# Sheet1.net
KiCad netlist of a schematic drawn in Altium Designer
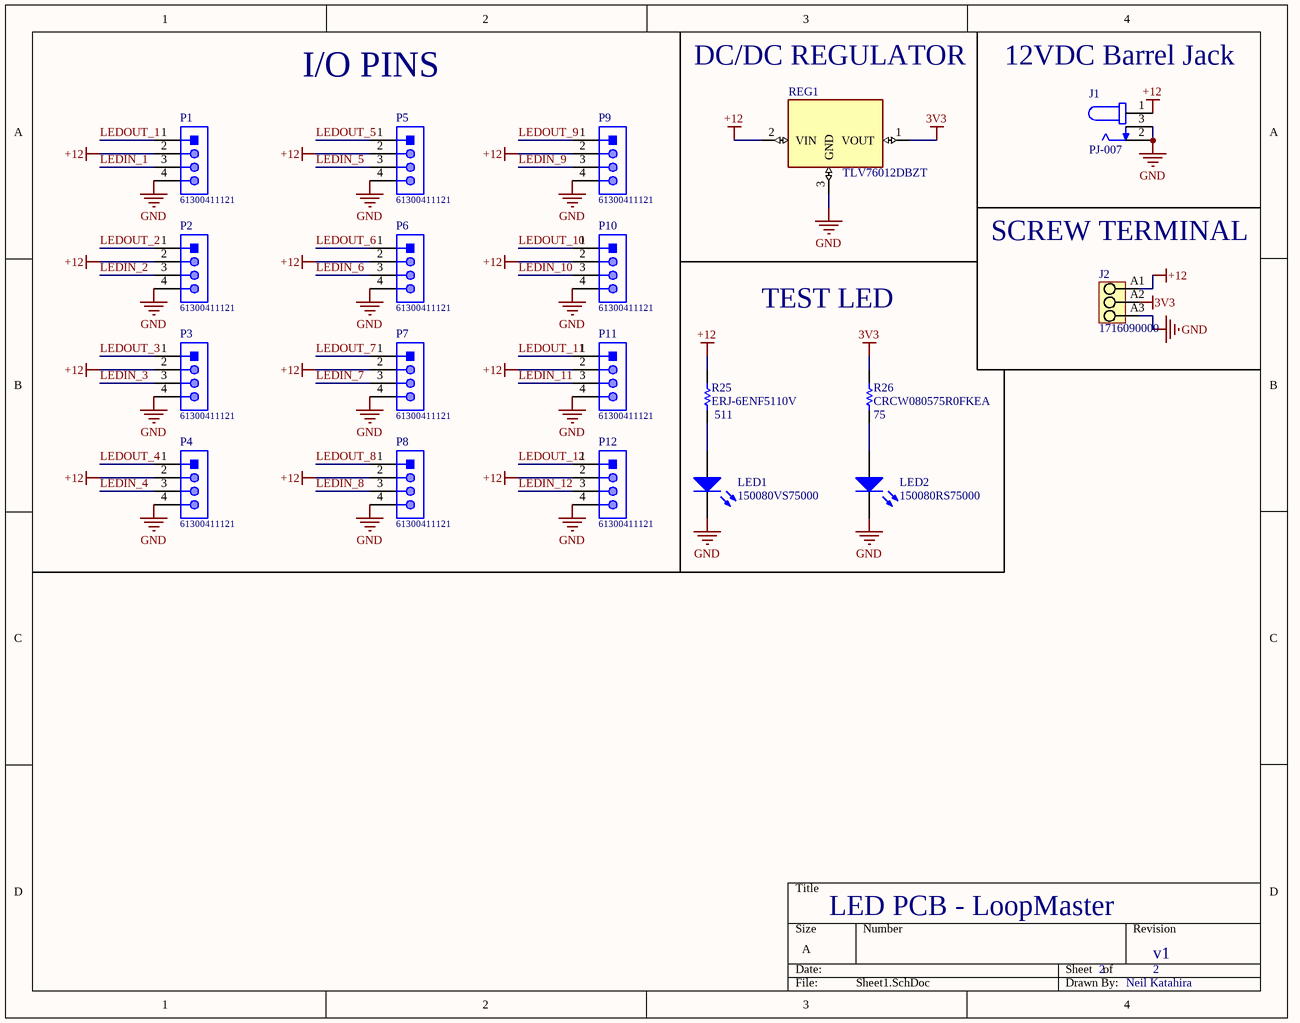
[diagram p0: Sheet1.SchDoc]

(export (version "E")
  (design (tool "Eeschema 10.0.6"))
  (components
    (comp (ref "J1")
      (value "PJ-007")
      (footprint "CUI_PJ-007")
      (description "1.3 x 4.2 mm, 2.0 A, Horizontal, Through Hole, Dc Power Jack Connector")
      (fields (field (name "MF") "CUI Devices"))
      (libsource (lib "LEDPCB") (part "PJ-007"))
    )
    (comp (ref "J2")
      (value "1716090000")
      (footprint "LM_5_08_90_03")
      (description "OMNIMATE Signal - series LM")
      (fields (field (name "MANUFACTURER") "Weidmueller"))
      (libsource (lib "Altium Content Vault") (part "Terminal_03_1x03"))
    )
    (comp (ref "LED1")
      (value "150080VS75000")
      (footprint "0805_A")
      (description "SMD mono-color Chip LED, WL-SMCW, Bright Green")
      (fields (field (name "MANUFACTURER") "Wuerth Elektronik"))
      (libsource (lib "Altium Content Vault") (part "WE-LED_K1A2-2"))
    )
    (comp (ref "LED2")
      (value "150080RS75000")
      (footprint "0805_A")
      (description "SMD mono-color Chip LED, WL-SMCW, Red")
      (fields (field (name "MANUFACTURER") "Wuerth Elektronik"))
      (libsource (lib "Altium Content Vault") (part "WE-LED_K1A2-2"))
    )
    (comp (ref "P1")
      (value "61300411121")
      (footprint "61300411121")
      (description "THT Vertical Pin Header WR-PHD, Pitch 2.54 mm, Single Row, 4 pins")
      (fields (field (name "MANUFACTURER") "Wurth Elektronik") (field (name "PUBLISHER") "WurthElektronik"))
      (libsource (lib "Altium Content Vault") (part "WE-CN-1P-M-R4"))
    )
    (comp (ref "P2")
      (value "61300411121")
      (footprint "61300411121")
      (description "THT Vertical Pin Header WR-PHD, Pitch 2.54 mm, Single Row, 4 pins")
      (fields (field (name "MANUFACTURER") "Wurth Elektronik") (field (name "PUBLISHER") "WurthElektronik"))
      (libsource (lib "Altium Content Vault") (part "WE-CN-1P-M-R4"))
    )
    (comp (ref "P3")
      (value "61300411121")
      (footprint "61300411121")
      (description "THT Vertical Pin Header WR-PHD, Pitch 2.54 mm, Single Row, 4 pins")
      (fields (field (name "MANUFACTURER") "Wurth Elektronik") (field (name "PUBLISHER") "WurthElektronik"))
      (libsource (lib "Altium Content Vault") (part "WE-CN-1P-M-R4"))
    )
    (comp (ref "P4")
      (value "61300411121")
      (footprint "61300411121")
      (description "THT Vertical Pin Header WR-PHD, Pitch 2.54 mm, Single Row, 4 pins")
      (fields (field (name "MANUFACTURER") "Wurth Elektronik") (field (name "PUBLISHER") "WurthElektronik"))
      (libsource (lib "Altium Content Vault") (part "WE-CN-1P-M-R4"))
    )
    (comp (ref "P5")
      (value "61300411121")
      (footprint "61300411121")
      (description "THT Vertical Pin Header WR-PHD, Pitch 2.54 mm, Single Row, 4 pins")
      (fields (field (name "MANUFACTURER") "Wurth Elektronik") (field (name "PUBLISHER") "WurthElektronik"))
      (libsource (lib "Altium Content Vault") (part "WE-CN-1P-M-R4"))
    )
    (comp (ref "P6")
      (value "61300411121")
      (footprint "61300411121")
      (description "THT Vertical Pin Header WR-PHD, Pitch 2.54 mm, Single Row, 4 pins")
      (fields (field (name "MANUFACTURER") "Wurth Elektronik") (field (name "PUBLISHER") "WurthElektronik"))
      (libsource (lib "Altium Content Vault") (part "WE-CN-1P-M-R4"))
    )
    (comp (ref "P7")
      (value "61300411121")
      (footprint "61300411121")
      (description "THT Vertical Pin Header WR-PHD, Pitch 2.54 mm, Single Row, 4 pins")
      (fields (field (name "MANUFACTURER") "Wurth Elektronik") (field (name "PUBLISHER") "WurthElektronik"))
      (libsource (lib "Altium Content Vault") (part "WE-CN-1P-M-R4"))
    )
    (comp (ref "P8")
      (value "61300411121")
      (footprint "61300411121")
      (description "THT Vertical Pin Header WR-PHD, Pitch 2.54 mm, Single Row, 4 pins")
      (fields (field (name "MANUFACTURER") "Wurth Elektronik") (field (name "PUBLISHER") "WurthElektronik"))
      (libsource (lib "Altium Content Vault") (part "WE-CN-1P-M-R4"))
    )
    (comp (ref "P9")
      (value "61300411121")
      (footprint "61300411121")
      (description "THT Vertical Pin Header WR-PHD, Pitch 2.54 mm, Single Row, 4 pins")
      (fields (field (name "MANUFACTURER") "Wurth Elektronik") (field (name "PUBLISHER") "WurthElektronik"))
      (libsource (lib "Altium Content Vault") (part "WE-CN-1P-M-R4"))
    )
    (comp (ref "P10")
      (value "61300411121")
      (footprint "61300411121")
      (description "THT Vertical Pin Header WR-PHD, Pitch 2.54 mm, Single Row, 4 pins")
      (fields (field (name "MANUFACTURER") "Wurth Elektronik") (field (name "PUBLISHER") "WurthElektronik"))
      (libsource (lib "Altium Content Vault") (part "WE-CN-1P-M-R4"))
    )
    (comp (ref "P11")
      (value "61300411121")
      (footprint "61300411121")
      (description "THT Vertical Pin Header WR-PHD, Pitch 2.54 mm, Single Row, 4 pins")
      (fields (field (name "MANUFACTURER") "Wurth Elektronik") (field (name "PUBLISHER") "WurthElektronik"))
      (libsource (lib "Altium Content Vault") (part "WE-CN-1P-M-R4"))
    )
    (comp (ref "P12")
      (value "61300411121")
      (footprint "61300411121")
      (description "THT Vertical Pin Header WR-PHD, Pitch 2.54 mm, Single Row, 4 pins")
      (fields (field (name "MANUFACTURER") "Wurth Elektronik") (field (name "PUBLISHER") "WurthElektronik"))
      (libsource (lib "Altium Content Vault") (part "WE-CN-1P-M-R4"))
    )
    (comp (ref "R25")
      (value "ERJ-6ENF5110V")
      (footprint "RESC2013X70X40ML20T20")
      (fields (field (name "MANUFACTURER") "Panasonic"))
      (libsource (lib "Altium Content Vault") (part "RES"))
    )
    (comp (ref "R26")
      (value "CRCW080575R0FKEA")
      (footprint "RESC2013X50X30ML20T20")
      (fields (field (name "MANUFACTURER") "Vishay Dale"))
      (libsource (lib "Altium Content Vault") (part "RES"))
    )
    (comp (ref "REG1")
      (value "TLV76012DBZT")
      (footprint "SOT23")
      (description "Linear Voltage Regulator IC 1 Output 100mA SOT-23-3")
      (fields (field (name "MF") "Texas Instruments"))
      (libsource (lib "LEDPCB") (part "TLV76012DBZT"))
    )
  )
  (nets
    (net (code "1") (name "+12") (class "Default")
      (node (ref "J1") (pin "1") (pinfunction "1_1") (pintype "passive"))
      (node (ref "J2") (pin "A1") (pinfunction "A1_A1") (pintype "passive"))
      (node (ref "P1") (pin "2") (pinfunction "2_2") (pintype "passive"))
      (node (ref "P10") (pin "2") (pinfunction "2_2") (pintype "passive"))
      (node (ref "P11") (pin "2") (pinfunction "2_2") (pintype "passive"))
      (node (ref "P12") (pin "2") (pinfunction "2_2") (pintype "passive"))
      (node (ref "P2") (pin "2") (pinfunction "2_2") (pintype "passive"))
      (node (ref "P3") (pin "2") (pinfunction "2_2") (pintype "passive"))
      (node (ref "P4") (pin "2") (pinfunction "2_2") (pintype "passive"))
      (node (ref "P5") (pin "2") (pinfunction "2_2") (pintype "passive"))
      (node (ref "P6") (pin "2") (pinfunction "2_2") (pintype "passive"))
      (node (ref "P7") (pin "2") (pinfunction "2_2") (pintype "passive"))
      (node (ref "P8") (pin "2") (pinfunction "2_2") (pintype "passive"))
      (node (ref "P9") (pin "2") (pinfunction "2_2") (pintype "passive"))
      (node (ref "R25") (pin "2") (pinfunction "2_2") (pintype "passive"))
      (node (ref "REG1") (pin "2") (pinfunction "VIN_2") (pintype "bidirectional"))
    )
    (net (code "2") (name "/LEDIN_1") (class "Default")
      (node (ref "P1") (pin "3") (pinfunction "3_3") (pintype "passive"))
    )
    (net (code "3") (name "/LEDIN_2") (class "Default")
      (node (ref "P2") (pin "3") (pinfunction "3_3") (pintype "passive"))
    )
    (net (code "4") (name "/LEDIN_3") (class "Default")
      (node (ref "P3") (pin "3") (pinfunction "3_3") (pintype "passive"))
    )
    (net (code "5") (name "/LEDIN_4") (class "Default")
      (node (ref "P4") (pin "3") (pinfunction "3_3") (pintype "passive"))
    )
    (net (code "6") (name "/LEDIN_5") (class "Default")
      (node (ref "P5") (pin "3") (pinfunction "3_3") (pintype "passive"))
    )
    (net (code "7") (name "/LEDIN_6") (class "Default")
      (node (ref "P6") (pin "3") (pinfunction "3_3") (pintype "passive"))
    )
    (net (code "8") (name "/LEDIN_7") (class "Default")
      (node (ref "P7") (pin "3") (pinfunction "3_3") (pintype "passive"))
    )
    (net (code "9") (name "/LEDIN_8") (class "Default")
      (node (ref "P8") (pin "3") (pinfunction "3_3") (pintype "passive"))
    )
    (net (code "10") (name "/LEDIN_9") (class "Default")
      (node (ref "P9") (pin "3") (pinfunction "3_3") (pintype "passive"))
    )
    (net (code "11") (name "/LEDIN_10") (class "Default")
      (node (ref "P10") (pin "3") (pinfunction "3_3") (pintype "passive"))
    )
    (net (code "12") (name "/LEDIN_11") (class "Default")
      (node (ref "P11") (pin "3") (pinfunction "3_3") (pintype "passive"))
    )
    (net (code "13") (name "/LEDIN_12") (class "Default")
      (node (ref "P12") (pin "3") (pinfunction "3_3") (pintype "passive"))
    )
    (net (code "14") (name "/LEDOUT_1") (class "Default")
      (node (ref "P1") (pin "1") (pinfunction "1_1") (pintype "passive"))
    )
    (net (code "15") (name "/LEDOUT_2") (class "Default")
      (node (ref "P2") (pin "1") (pinfunction "1_1") (pintype "passive"))
    )
    (net (code "16") (name "/LEDOUT_3") (class "Default")
      (node (ref "P3") (pin "1") (pinfunction "1_1") (pintype "passive"))
    )
    (net (code "17") (name "/LEDOUT_4") (class "Default")
      (node (ref "P4") (pin "1") (pinfunction "1_1") (pintype "passive"))
    )
    (net (code "18") (name "/LEDOUT_5") (class "Default")
      (node (ref "P5") (pin "1") (pinfunction "1_1") (pintype "passive"))
    )
    (net (code "19") (name "/LEDOUT_6") (class "Default")
      (node (ref "P6") (pin "1") (pinfunction "1_1") (pintype "passive"))
    )
    (net (code "20") (name "/LEDOUT_7") (class "Default")
      (node (ref "P7") (pin "1") (pinfunction "1_1") (pintype "passive"))
    )
    (net (code "21") (name "/LEDOUT_8") (class "Default")
      (node (ref "P8") (pin "1") (pinfunction "1_1") (pintype "passive"))
    )
    (net (code "22") (name "/LEDOUT_9") (class "Default")
      (node (ref "P9") (pin "1") (pinfunction "1_1") (pintype "passive"))
    )
    (net (code "23") (name "/LEDOUT_10") (class "Default")
      (node (ref "P10") (pin "1") (pinfunction "1_1") (pintype "passive"))
    )
    (net (code "24") (name "/LEDOUT_11") (class "Default")
      (node (ref "P11") (pin "1") (pinfunction "1_1") (pintype "passive"))
    )
    (net (code "25") (name "/LEDOUT_12") (class "Default")
      (node (ref "P12") (pin "1") (pinfunction "1_1") (pintype "passive"))
    )
    (net (code "26") (name "3V3") (class "Default")
      (node (ref "J2") (pin "A2") (pinfunction "A2_A2") (pintype "passive"))
      (node (ref "R26") (pin "2") (pinfunction "2_2") (pintype "passive"))
      (node (ref "REG1") (pin "1") (pinfunction "VOUT_1") (pintype "bidirectional"))
    )
    (net (code "27") (name "GND") (class "Default")
      (node (ref "J1") (pin "2") (pinfunction "2_2") (pintype "passive"))
      (node (ref "J1") (pin "3") (pinfunction "3_3") (pintype "passive"))
      (node (ref "J2") (pin "A3") (pinfunction "A3_A3") (pintype "passive"))
      (node (ref "LED1") (pin "1") (pinfunction "K_1") (pintype "passive"))
      (node (ref "LED2") (pin "1") (pinfunction "K_1") (pintype "passive"))
      (node (ref "P1") (pin "4") (pinfunction "4_4") (pintype "passive"))
      (node (ref "P10") (pin "4") (pinfunction "4_4") (pintype "passive"))
      (node (ref "P11") (pin "4") (pinfunction "4_4") (pintype "passive"))
      (node (ref "P12") (pin "4") (pinfunction "4_4") (pintype "passive"))
      (node (ref "P2") (pin "4") (pinfunction "4_4") (pintype "passive"))
      (node (ref "P3") (pin "4") (pinfunction "4_4") (pintype "passive"))
      (node (ref "P4") (pin "4") (pinfunction "4_4") (pintype "passive"))
      (node (ref "P5") (pin "4") (pinfunction "4_4") (pintype "passive"))
      (node (ref "P6") (pin "4") (pinfunction "4_4") (pintype "passive"))
      (node (ref "P7") (pin "4") (pinfunction "4_4") (pintype "passive"))
      (node (ref "P8") (pin "4") (pinfunction "4_4") (pintype "passive"))
      (node (ref "P9") (pin "4") (pinfunction "4_4") (pintype "passive"))
      (node (ref "REG1") (pin "3") (pinfunction "GND_3") (pintype "bidirectional"))
    )
    (net (code "28") (name "Net-(LED1-A)") (class "Default")
      (node (ref "LED1") (pin "2") (pinfunction "A_2") (pintype "passive"))
      (node (ref "R25") (pin "1") (pinfunction "1_1") (pintype "passive"))
    )
    (net (code "29") (name "Net-(LED2-A)") (class "Default")
      (node (ref "LED2") (pin "2") (pinfunction "A_2") (pintype "passive"))
      (node (ref "R26") (pin "1") (pinfunction "1_1") (pintype "passive"))
    )
  )
)
